# LEDs_FMU_REV_1A.net
KiCad netlist of a schematic drawn in Altium Designer
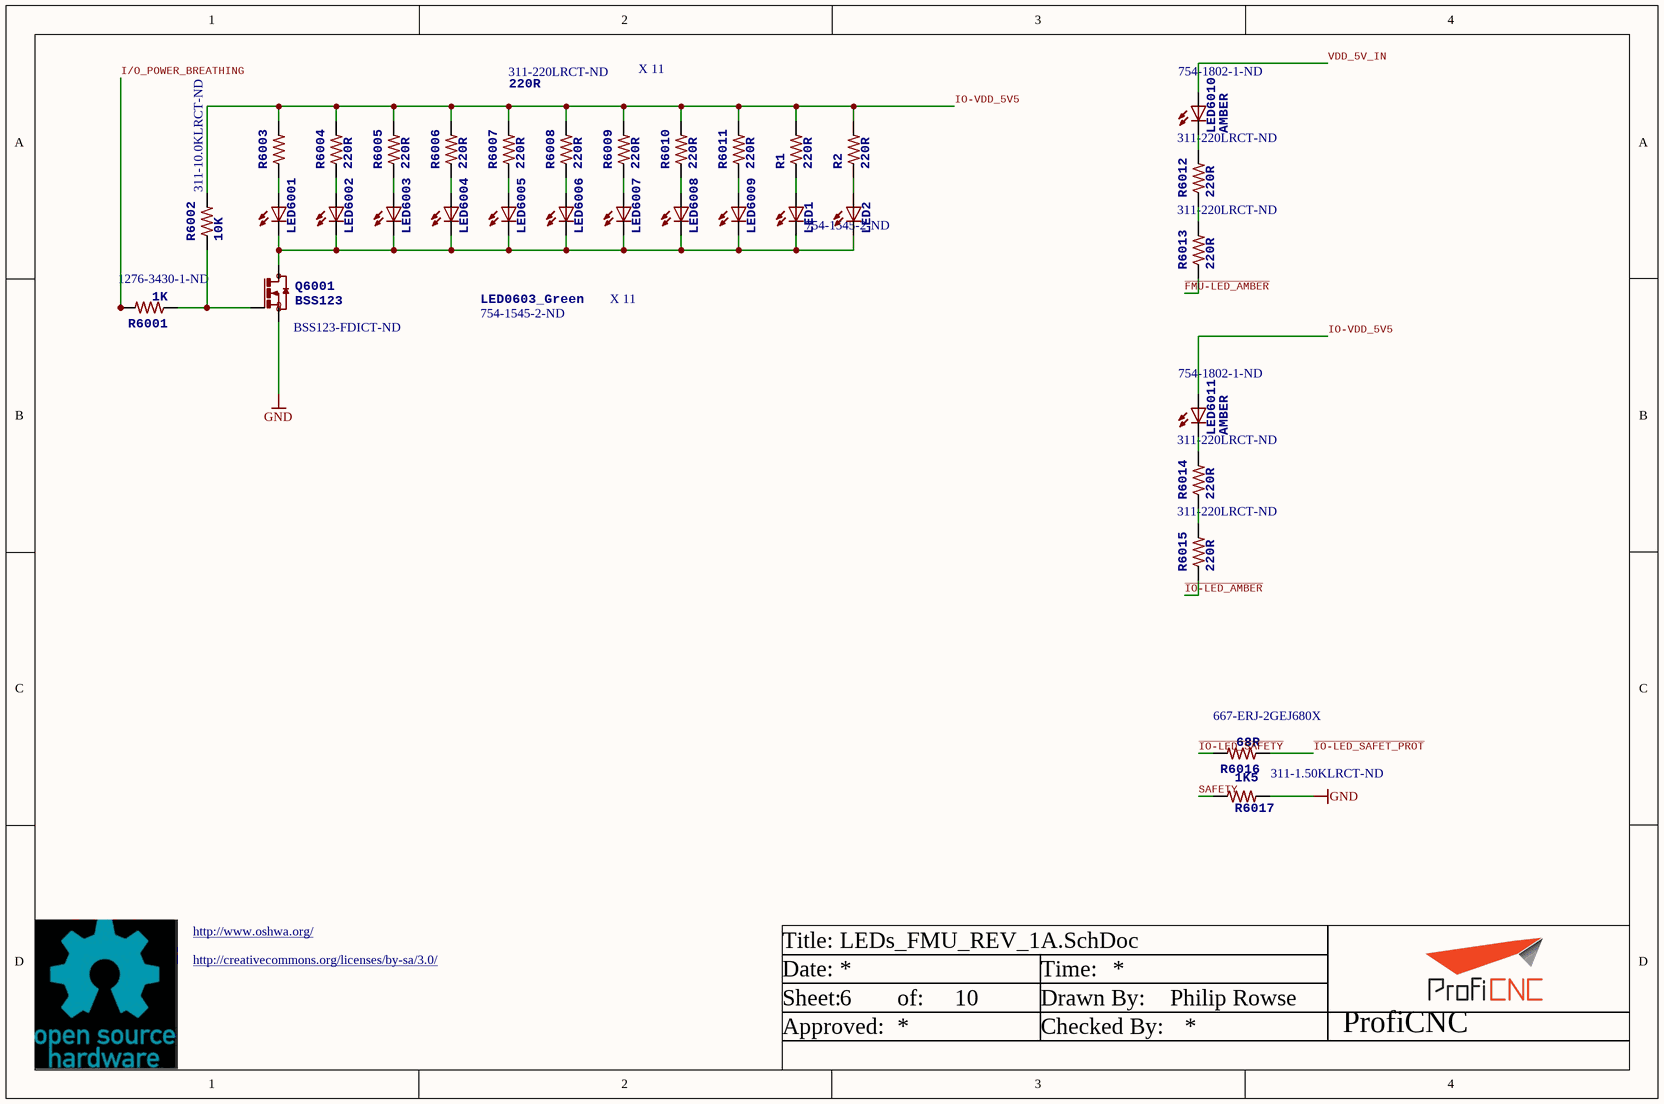
[diagram p0: LEDs_FMU_REV_1A.SchDoc]

(export (version "E")
  (design (tool "Eeschema 10.0.6"))
  (components
    (comp (ref "LED1")
      (value "LED0603_Green")
      (footprint "0603-LED-Blue")
      (description "LED GREEN ROUND CLEAR SMD")
      (fields
        (field (name "SUPPLIER PART NUMBER 1") "754-1545-2-ND")
        (field (name "3DR_PARTNO") "ECM0494")
        (field (name "PARTNO") "APTD1608CGCK")
      )
      (libsource (lib "pixhawk2") (part "LED0603_Blue"))
    )
    (comp (ref "LED2")
      (value "LED0603_Green")
      (footprint "0603-LED-Blue")
      (description "LED GREEN ROUND CLEAR SMD")
      (fields (field (name "3DR_PARTNO") "ECM0494") (field (name "PARTNO") "APTD1608CGCK"))
      (libsource (lib "pixhawk2") (part "LED0603_Blue"))
    )
    (comp (ref "LED6001")
      (value "LED0603_Green")
      (footprint "0603-LED-Blue")
      (description "LED GREEN ROUND CLEAR SMD")
      (fields
        (field (name "SUPPLIER PART NUMBER 1") "754-1545-2-ND")
        (field (name "3DR_PARTNO") "ECM0494")
        (field (name "PARTNO") "APTD1608CGCK")
      )
      (libsource (lib "pixhawk2") (part "LED0603_Blue"))
    )
    (comp (ref "LED6002")
      (value "LED0603_Green")
      (footprint "0603-LED-Blue")
      (description "LED GREEN ROUND CLEAR SMD")
      (fields (field (name "3DR_PARTNO") "ECM0494") (field (name "PARTNO") "APTD1608CGCK"))
      (libsource (lib "pixhawk2") (part "LED0603_Blue"))
    )
    (comp (ref "LED6003")
      (value "LED0603_Green")
      (footprint "0603-LED-Blue")
      (description "LED GREEN ROUND CLEAR SMD")
      (fields (field (name "3DR_PARTNO") "ECM0494") (field (name "PARTNO") "APTD1608CGCK"))
      (libsource (lib "pixhawk2") (part "LED0603_Blue"))
    )
    (comp (ref "LED6004")
      (value "LED0603_Green")
      (footprint "0603-LED-Blue")
      (description "LED GREEN ROUND CLEAR SMD")
      (fields (field (name "3DR_PARTNO") "ECM0494") (field (name "PARTNO") "APTD1608CGCK"))
      (libsource (lib "pixhawk2") (part "LED0603_Blue"))
    )
    (comp (ref "LED6005")
      (value "LED0603_Green")
      (footprint "0603-LED-Blue")
      (description "LED GREEN ROUND CLEAR SMD")
      (fields (field (name "3DR_PARTNO") "ECM0494") (field (name "PARTNO") "APTD1608CGCK"))
      (libsource (lib "pixhawk2") (part "LED0603_Blue"))
    )
    (comp (ref "LED6006")
      (value "LED0603_Green")
      (footprint "0603-LED-Blue")
      (description "LED GREEN ROUND CLEAR SMD")
      (fields (field (name "3DR_PARTNO") "ECM0494") (field (name "PARTNO") "APTD1608CGCK"))
      (libsource (lib "pixhawk2") (part "LED0603_Blue"))
    )
    (comp (ref "LED6007")
      (value "LED0603_Green")
      (footprint "0603-LED-Blue")
      (description "LED GREEN ROUND CLEAR SMD")
      (fields (field (name "3DR_PARTNO") "ECM0494") (field (name "PARTNO") "APTD1608CGCK"))
      (libsource (lib "pixhawk2") (part "LED0603_Blue"))
    )
    (comp (ref "LED6008")
      (value "LED0603_Green")
      (footprint "0603-LED-Blue")
      (description "LED GREEN ROUND CLEAR SMD")
      (fields (field (name "3DR_PARTNO") "ECM0494") (field (name "PARTNO") "APTD1608CGCK"))
      (libsource (lib "pixhawk2") (part "LED0603_Blue"))
    )
    (comp (ref "LED6009")
      (value "LED0603_Green")
      (footprint "0603-LED-Blue")
      (description "LED GREEN ROUND CLEAR SMD")
      (fields (field (name "3DR_PARTNO") "ECM0494") (field (name "PARTNO") "APTD1608CGCK"))
      (libsource (lib "pixhawk2") (part "LED0603_Blue"))
    )
    (comp (ref "LED6010")
      (value "AMBER")
      (footprint "0603-LED")
      (description "LED 1.6X0.8 DOME ORN CLEAR SMD")
      (fields
        (field (name "PARTNO") "APTD1608SECK")
        (field (name "SUPPLIER PART NUMBER 1") "754-1802-1-ND")
        (field (name "3DR_PARTNO") "ECM0515")
      )
      (libsource (lib "pixhawk2") (part "LED0603"))
    )
    (comp (ref "LED6011")
      (value "AMBER")
      (footprint "0603-LED")
      (description "LED 1.6X0.8 DOME ORN CLEAR SMD")
      (fields
        (field (name "PARTNO") "APTD1608SECK")
        (field (name "SUPPLIER PART NUMBER 1") "754-1802-1-ND")
        (field (name "3DR_PARTNO") "ECM0515")
      )
      (libsource (lib "pixhawk2") (part "LED0603"))
    )
    (comp (ref "Q6001")
      (value "BSS123")
      (footprint "SOT23")
      (description "MOSFET N-CH 100V 170MA SOT23-3")
      (fields (field (name "SUPPLIER PART NUMBER 1") "BSS123-FDICT-ND") (field (name "3DR_PARTNO") "ECM0547"))
      (libsource (lib "transistor-small-signal") (part "BSS123"))
    )
    (comp (ref "R1")
      (value "220R")
      (footprint "0402-RES")
      (description "RES 220 OHM 1/16W 1% 0402 SMD")
      (fields (field (name "PARTNO") "RC0402FR-07220RL") (field (name "3DR_PARTNO") "ECM0821"))
      (libsource (lib "pixhawk2") (part "RESISTOR0402-RES"))
    )
    (comp (ref "R2")
      (value "220R")
      (footprint "0402-RES")
      (description "RES 220 OHM 1/16W 1% 0402 SMD")
      (fields (field (name "PARTNO") "RC0402FR-07220RL") (field (name "3DR_PARTNO") "ECM0821"))
      (libsource (lib "pixhawk2") (part "RESISTOR0402-RES"))
    )
    (comp (ref "R6001")
      (value "1K")
      (footprint "0402-RES")
      (description "RES 1K OHM 1/16W 1% 0402")
      (fields
        (field (name "PARTNO") "RC1005F102CS")
        (field (name "SUPPLIER PART NUMBER 1") "1276-3430-1-ND")
        (field (name "3DR_PARTNO") "ECM0804")
      )
      (libsource (lib "pixhawk2") (part "RESISTOR0402-RES"))
    )
    (comp (ref "R6002")
      (value "10K")
      (footprint "0402-RES")
      (description "RES 10K OHM 1/16W 1% 0402 SMD")
      (fields
        (field (name "PARTNO") "RC0402FR-0710KL")
        (field (name "SUPPLIER PART NUMBER 1") "311-10.0KLRCT-ND")
        (field (name "3DR_PARTNO") "ECM0800")
      )
      (libsource (lib "pixhawk2") (part "RESISTOR0402-RES"))
    )
    (comp (ref "R6003")
      (value "220R")
      (footprint "0402-RES")
      (description "RES 220 OHM 1/16W 1% 0402 SMD")
      (fields
        (field (name "PARTNO") "RC0402FR-07220RL")
        (field (name "SUPPLIER PART NUMBER 1") "311-220LRCT-ND")
        (field (name "3DR_PARTNO") "ECM0821")
      )
      (libsource (lib "pixhawk2") (part "RESISTOR0402-RES"))
    )
    (comp (ref "R6004")
      (value "220R")
      (footprint "0402-RES")
      (description "RES 220 OHM 1/16W 1% 0402 SMD")
      (fields (field (name "PARTNO") "RC0402FR-07220RL") (field (name "3DR_PARTNO") "ECM0821"))
      (libsource (lib "pixhawk2") (part "RESISTOR0402-RES"))
    )
    (comp (ref "R6005")
      (value "220R")
      (footprint "0402-RES")
      (description "RES 220 OHM 1/16W 1% 0402 SMD")
      (fields (field (name "PARTNO") "RC0402FR-07220RL") (field (name "3DR_PARTNO") "ECM0821"))
      (libsource (lib "pixhawk2") (part "RESISTOR0402-RES"))
    )
    (comp (ref "R6006")
      (value "220R")
      (footprint "0402-RES")
      (description "RES 220 OHM 1/16W 1% 0402 SMD")
      (fields (field (name "PARTNO") "RC0402FR-07220RL") (field (name "3DR_PARTNO") "ECM0821"))
      (libsource (lib "pixhawk2") (part "RESISTOR0402-RES"))
    )
    (comp (ref "R6007")
      (value "220R")
      (footprint "0402-RES")
      (description "RES 220 OHM 1/16W 1% 0402 SMD")
      (fields (field (name "PARTNO") "RC0402FR-07220RL") (field (name "3DR_PARTNO") "ECM0821"))
      (libsource (lib "pixhawk2") (part "RESISTOR0402-RES"))
    )
    (comp (ref "R6008")
      (value "220R")
      (footprint "0402-RES")
      (description "RES 220 OHM 1/16W 1% 0402 SMD")
      (fields (field (name "PARTNO") "RC0402FR-07220RL") (field (name "3DR_PARTNO") "ECM0821"))
      (libsource (lib "pixhawk2") (part "RESISTOR0402-RES"))
    )
    (comp (ref "R6009")
      (value "220R")
      (footprint "0402-RES")
      (description "RES 220 OHM 1/16W 1% 0402 SMD")
      (fields (field (name "PARTNO") "RC0402FR-07220RL") (field (name "3DR_PARTNO") "ECM0821"))
      (libsource (lib "pixhawk2") (part "RESISTOR0402-RES"))
    )
    (comp (ref "R6010")
      (value "220R")
      (footprint "0402-RES")
      (description "RES 220 OHM 1/16W 1% 0402 SMD")
      (fields (field (name "PARTNO") "RC0402FR-07220RL") (field (name "3DR_PARTNO") "ECM0821"))
      (libsource (lib "pixhawk2") (part "RESISTOR0402-RES"))
    )
    (comp (ref "R6011")
      (value "220R")
      (footprint "0402-RES")
      (description "RES 220 OHM 1/16W 1% 0402 SMD")
      (fields (field (name "PARTNO") "RC0402FR-07220RL") (field (name "3DR_PARTNO") "ECM0821"))
      (libsource (lib "pixhawk2") (part "RESISTOR0402-RES"))
    )
    (comp (ref "R6012")
      (value "220R")
      (footprint "0402-RES")
      (description "RES 220 OHM 1/16W 1% 0402 SMD")
      (fields
        (field (name "PARTNO") "RC0402FR-07220RL")
        (field (name "SUPPLIER PART NUMBER 1") "311-220LRCT-ND")
        (field (name "3DR_PARTNO") "ECM0821")
      )
      (libsource (lib "pixhawk2") (part "RESISTOR0402-RES"))
    )
    (comp (ref "R6013")
      (value "220R")
      (footprint "0402-RES")
      (description "RES 220 OHM 1/16W 1% 0402 SMD")
      (fields
        (field (name "PARTNO") "RC0402FR-07220RL")
        (field (name "SUPPLIER PART NUMBER 1") "311-220LRCT-ND")
        (field (name "3DR_PARTNO") "ECM0821")
      )
      (libsource (lib "pixhawk2") (part "RESISTOR0402-RES"))
    )
    (comp (ref "R6014")
      (value "220R")
      (footprint "0402-RES")
      (description "RES 220 OHM 1/16W 1% 0402 SMD")
      (fields
        (field (name "PARTNO") "RC0402FR-07220RL")
        (field (name "SUPPLIER PART NUMBER 1") "311-220LRCT-ND")
        (field (name "3DR_PARTNO") "ECM0821")
      )
      (libsource (lib "pixhawk2") (part "RESISTOR0402-RES"))
    )
    (comp (ref "R6015")
      (value "220R")
      (footprint "0402-RES")
      (description "RES 220 OHM 1/16W 1% 0402 SMD")
      (fields
        (field (name "PARTNO") "RC0402FR-07220RL")
        (field (name "SUPPLIER PART NUMBER 1") "311-220LRCT-ND")
        (field (name "3DR_PARTNO") "ECM0821")
      )
      (libsource (lib "pixhawk2") (part "RESISTOR0402-RES"))
    )
    (comp (ref "R6016")
      (value "68R")
      (footprint "0402-RES")
      (description "Thick Film Resistors - SMD 0402 68ohms 5% Tol")
      (fields
        (field (name "PARTNO") "ERJ-2GEJ680X")
        (field (name "SUPPLIER PART NUMBER 1") "667-ERJ-2GEJ680X")
        (field (name "3DR_PARTNO") "ECM0816")
      )
      (libsource (lib "pixhawk2") (part "RESISTOR0402-RES"))
    )
    (comp (ref "R6017")
      (value "1K5")
      (footprint "0402-RES")
      (description "RES 1.5K OHM 1/16W 1% 0402 SMD")
      (fields
        (field (name "SUPPLIER PART NUMBER 1") "311-1.50KLRCT-ND")
        (field (name "3DR_PARTNO") "ECM0803")
        (field (name "PARTNO") "RC0402FR-071K5L")
      )
      (libsource (lib "pixhawk2") (part "RESISTOR0402-RES"))
    )
  )
  (nets
    (net (code "1") (name "/IO-VDD_5V5") (class "Default")
      (node (ref "LED6011") (pin "A") (pinfunction "A_A") (pintype "passive"))
      (node (ref "R1") (pin "P$2") (pinfunction "2_P$2") (pintype "passive"))
      (node (ref "R2") (pin "P$2") (pinfunction "2_P$2") (pintype "passive"))
      (node (ref "R6002") (pin "P$2") (pinfunction "2_P$2") (pintype "passive"))
      (node (ref "R6003") (pin "P$2") (pinfunction "2_P$2") (pintype "passive"))
      (node (ref "R6004") (pin "P$2") (pinfunction "2_P$2") (pintype "passive"))
      (node (ref "R6005") (pin "P$2") (pinfunction "2_P$2") (pintype "passive"))
      (node (ref "R6006") (pin "P$2") (pinfunction "2_P$2") (pintype "passive"))
      (node (ref "R6007") (pin "P$2") (pinfunction "2_P$2") (pintype "passive"))
      (node (ref "R6008") (pin "P$2") (pinfunction "2_P$2") (pintype "passive"))
      (node (ref "R6009") (pin "P$2") (pinfunction "2_P$2") (pintype "passive"))
      (node (ref "R6010") (pin "P$2") (pinfunction "2_P$2") (pintype "passive"))
      (node (ref "R6011") (pin "P$2") (pinfunction "2_P$2") (pintype "passive"))
    )
    (net (code "2") (name "/I{slash}O_POWER_BREATHING") (class "Default")
      (node (ref "R6001") (pin "P$2") (pinfunction "2_P$2") (pintype "passive"))
    )
    (net (code "3") (name "/SAFETY") (class "Default")
      (node (ref "R6017") (pin "P$1") (pinfunction "1_P$1") (pintype "passive"))
    )
    (net (code "4") (name "/VDD_5V_IN") (class "Default")
      (node (ref "LED6010") (pin "A") (pinfunction "A_A") (pintype "passive"))
    )
    (net (code "5") (name "/~{FMU-LED_AMBER}") (class "Default")
      (node (ref "R6013") (pin "P$1") (pinfunction "1_P$1") (pintype "passive"))
    )
    (net (code "6") (name "/~{IO-LED_AMBER}") (class "Default")
      (node (ref "R6015") (pin "P$1") (pinfunction "1_P$1") (pintype "passive"))
    )
    (net (code "7") (name "/~{IO-LED_SAFETY}") (class "Default")
      (node (ref "R6016") (pin "P$2") (pinfunction "2_P$2") (pintype "passive"))
    )
    (net (code "8") (name "/~{IO-LED_SAFET_PROT}") (class "Default")
      (node (ref "R6016") (pin "P$1") (pinfunction "1_P$1") (pintype "passive"))
    )
    (net (code "9") (name "GND") (class "Default")
      (node (ref "Q6001") (pin "2") (pinfunction "S_2") (pintype "passive"))
      (node (ref "R6017") (pin "P$2") (pinfunction "2_P$2") (pintype "passive"))
    )
    (net (code "10") (name "Net-(Q6001-D)") (class "Default")
      (node (ref "LED1") (pin "C") (pinfunction "C_C") (pintype "passive"))
      (node (ref "LED2") (pin "C") (pinfunction "C_C") (pintype "passive"))
      (node (ref "LED6001") (pin "C") (pinfunction "C_C") (pintype "passive"))
      (node (ref "LED6002") (pin "C") (pinfunction "C_C") (pintype "passive"))
      (node (ref "LED6003") (pin "C") (pinfunction "C_C") (pintype "passive"))
      (node (ref "LED6004") (pin "C") (pinfunction "C_C") (pintype "passive"))
      (node (ref "LED6005") (pin "C") (pinfunction "C_C") (pintype "passive"))
      (node (ref "LED6006") (pin "C") (pinfunction "C_C") (pintype "passive"))
      (node (ref "LED6007") (pin "C") (pinfunction "C_C") (pintype "passive"))
      (node (ref "LED6008") (pin "C") (pinfunction "C_C") (pintype "passive"))
      (node (ref "LED6009") (pin "C") (pinfunction "C_C") (pintype "passive"))
      (node (ref "Q6001") (pin "3") (pinfunction "D_3") (pintype "passive"))
    )
    (net (code "11") (name "Net-(Q6001-G)") (class "Default")
      (node (ref "Q6001") (pin "1") (pinfunction "G_1") (pintype "passive"))
      (node (ref "R6001") (pin "P$1") (pinfunction "1_P$1") (pintype "passive"))
      (node (ref "R6002") (pin "P$1") (pinfunction "1_P$1") (pintype "passive"))
    )
    (net (code "12") (name "Net-(R1-1)") (class "Default")
      (node (ref "LED1") (pin "A") (pinfunction "A_A") (pintype "passive"))
      (node (ref "R1") (pin "P$1") (pinfunction "1_P$1") (pintype "passive"))
    )
    (net (code "13") (name "Net-(R2-1)") (class "Default")
      (node (ref "LED2") (pin "A") (pinfunction "A_A") (pintype "passive"))
      (node (ref "R2") (pin "P$1") (pinfunction "1_P$1") (pintype "passive"))
    )
    (net (code "14") (name "Net-(R6003-1)") (class "Default")
      (node (ref "LED6001") (pin "A") (pinfunction "A_A") (pintype "passive"))
      (node (ref "R6003") (pin "P$1") (pinfunction "1_P$1") (pintype "passive"))
    )
    (net (code "15") (name "Net-(R6004-1)") (class "Default")
      (node (ref "LED6002") (pin "A") (pinfunction "A_A") (pintype "passive"))
      (node (ref "R6004") (pin "P$1") (pinfunction "1_P$1") (pintype "passive"))
    )
    (net (code "16") (name "Net-(R6005-1)") (class "Default")
      (node (ref "LED6003") (pin "A") (pinfunction "A_A") (pintype "passive"))
      (node (ref "R6005") (pin "P$1") (pinfunction "1_P$1") (pintype "passive"))
    )
    (net (code "17") (name "Net-(R6006-1)") (class "Default")
      (node (ref "LED6004") (pin "A") (pinfunction "A_A") (pintype "passive"))
      (node (ref "R6006") (pin "P$1") (pinfunction "1_P$1") (pintype "passive"))
    )
    (net (code "18") (name "Net-(R6007-1)") (class "Default")
      (node (ref "LED6005") (pin "A") (pinfunction "A_A") (pintype "passive"))
      (node (ref "R6007") (pin "P$1") (pinfunction "1_P$1") (pintype "passive"))
    )
    (net (code "19") (name "Net-(R6008-1)") (class "Default")
      (node (ref "LED6006") (pin "A") (pinfunction "A_A") (pintype "passive"))
      (node (ref "R6008") (pin "P$1") (pinfunction "1_P$1") (pintype "passive"))
    )
    (net (code "20") (name "Net-(R6009-1)") (class "Default")
      (node (ref "LED6007") (pin "A") (pinfunction "A_A") (pintype "passive"))
      (node (ref "R6009") (pin "P$1") (pinfunction "1_P$1") (pintype "passive"))
    )
    (net (code "21") (name "Net-(R6010-1)") (class "Default")
      (node (ref "LED6008") (pin "A") (pinfunction "A_A") (pintype "passive"))
      (node (ref "R6010") (pin "P$1") (pinfunction "1_P$1") (pintype "passive"))
    )
    (net (code "22") (name "Net-(R6011-1)") (class "Default")
      (node (ref "LED6009") (pin "A") (pinfunction "A_A") (pintype "passive"))
      (node (ref "R6011") (pin "P$1") (pinfunction "1_P$1") (pintype "passive"))
    )
    (net (code "23") (name "Net-(R6012-1)") (class "Default")
      (node (ref "R6012") (pin "P$1") (pinfunction "1_P$1") (pintype "passive"))
      (node (ref "R6013") (pin "P$2") (pinfunction "2_P$2") (pintype "passive"))
    )
    (net (code "24") (name "Net-(R6012-2)") (class "Default")
      (node (ref "LED6010") (pin "C") (pinfunction "C_C") (pintype "passive"))
      (node (ref "R6012") (pin "P$2") (pinfunction "2_P$2") (pintype "passive"))
    )
    (net (code "25") (name "Net-(R6014-1)") (class "Default")
      (node (ref "R6014") (pin "P$1") (pinfunction "1_P$1") (pintype "passive"))
      (node (ref "R6015") (pin "P$2") (pinfunction "2_P$2") (pintype "passive"))
    )
    (net (code "26") (name "Net-(R6014-2)") (class "Default")
      (node (ref "LED6011") (pin "C") (pinfunction "C_C") (pintype "passive"))
      (node (ref "R6014") (pin "P$2") (pinfunction "2_P$2") (pintype "passive"))
    )
  )
)
